# 51.net
KiCad netlist of a schematic drawn in EasyEDA Pro
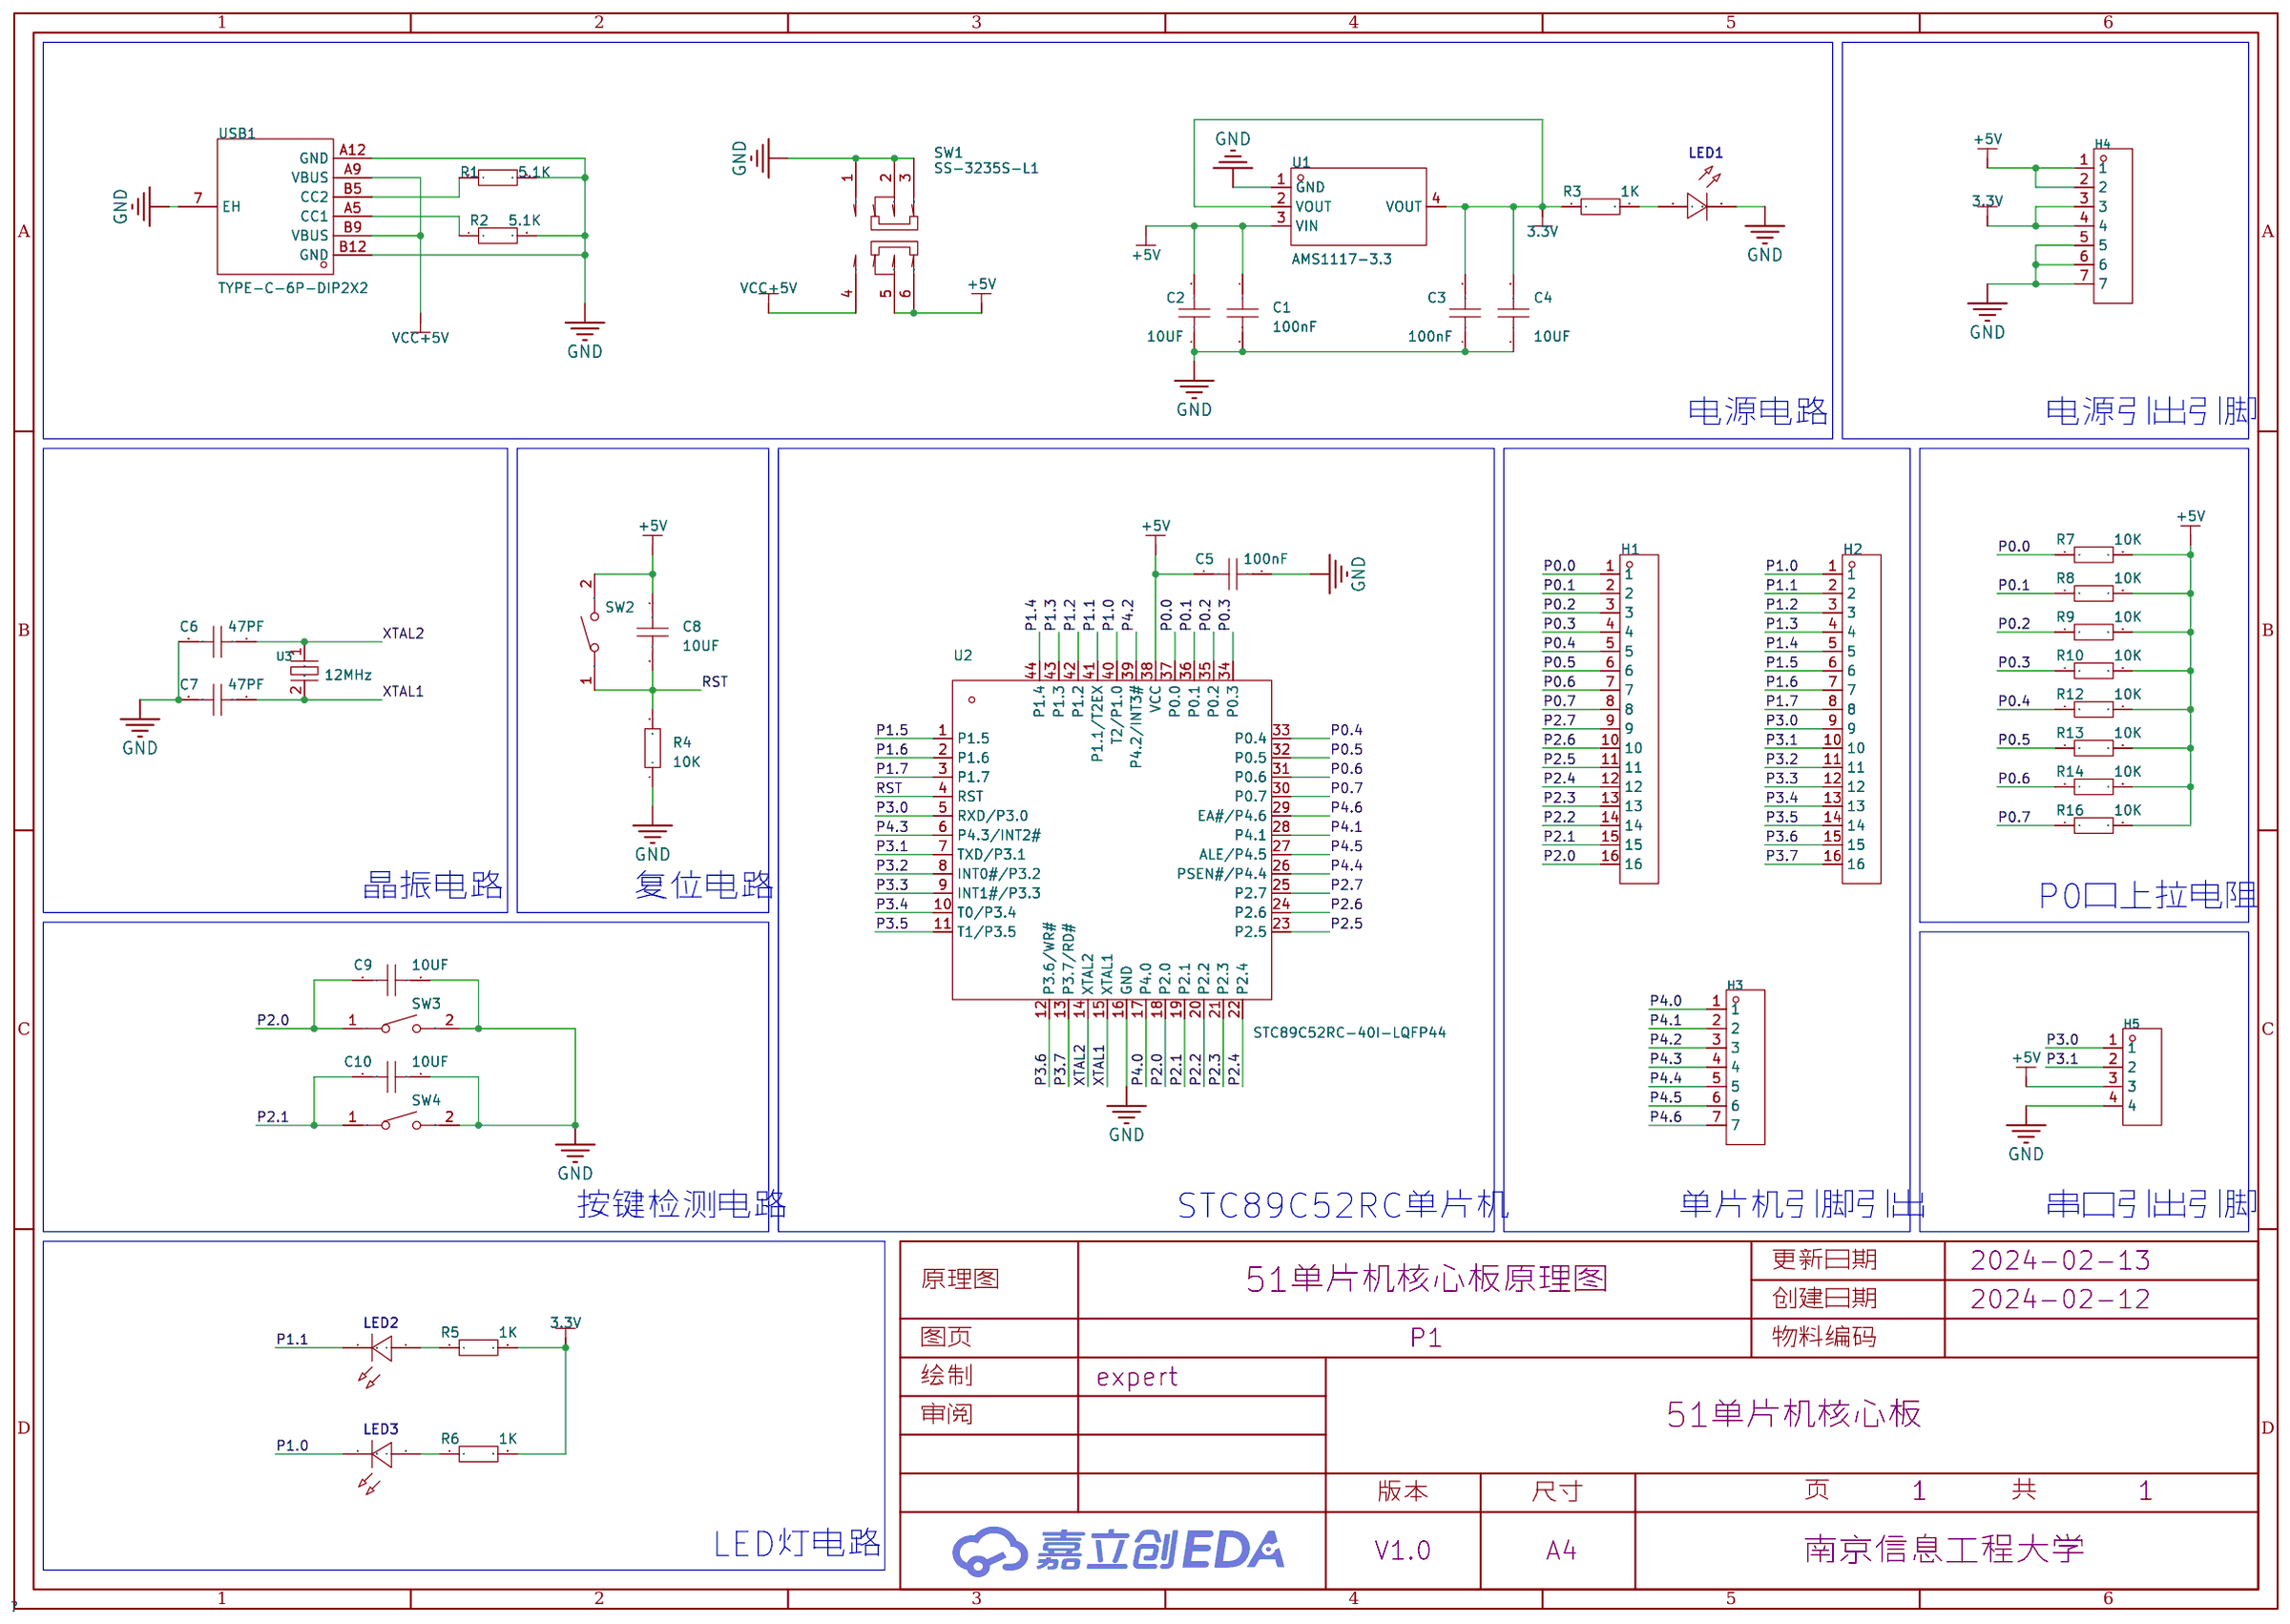
[diagram p0: schematic sheet]

(export (version "E")
  (design (tool "Eeschema 10.0.6"))
  (components
    (comp (ref "C1")
      (value "100nF")
      (footprint "easyedapro:C0805")
      (libsource (lib "easyedapro") (part "CapAcitance"))
    )
    (comp (ref "C2")
      (value "10UF")
      (footprint "easyedapro:C0805")
      (libsource (lib "easyedapro") (part "CapAcitance"))
    )
    (comp (ref "C3")
      (value "100nF")
      (footprint "easyedapro:C0805")
      (libsource (lib "easyedapro") (part "CapAcitance"))
    )
    (comp (ref "C4")
      (value "10UF")
      (footprint "easyedapro:C0805")
      (libsource (lib "easyedapro") (part "CapAcitance"))
    )
    (comp (ref "C5")
      (value "100nF")
      (footprint "easyedapro:C0805")
      (libsource (lib "easyedapro") (part "CapAcitance"))
    )
    (comp (ref "C6")
      (value "47PF")
      (footprint "easyedapro:C0805")
      (libsource (lib "easyedapro") (part "CapAcitance"))
    )
    (comp (ref "C7")
      (value "47PF")
      (footprint "easyedapro:C0805")
      (libsource (lib "easyedapro") (part "CapAcitance"))
    )
    (comp (ref "C8")
      (value "10UF")
      (footprint "easyedapro:C0805")
      (libsource (lib "easyedapro") (part "CapAcitance"))
    )
    (comp (ref "C9")
      (value "10UF")
      (footprint "easyedapro:C0805")
      (libsource (lib "easyedapro") (part "CapAcitance"))
    )
    (comp (ref "C10")
      (value "10UF")
      (footprint "easyedapro:C0805")
      (libsource (lib "easyedapro") (part "CapAcitance"))
    )
    (comp (ref "H1")
      (value "~")
      (footprint "easyedapro:HDR-TH_16P-P2.54-V-M")
      (libsource (lib "easyedapro") (part "HDR_2.54-1x16P"))
    )
    (comp (ref "H2")
      (value "~")
      (footprint "easyedapro:HDR-TH_16P-P2.54-V-M")
      (libsource (lib "easyedapro") (part "HDR_2.54-1x16P"))
    )
    (comp (ref "H3")
      (value "~")
      (footprint "easyedapro:HDR-TH_7P-P2.54-V-M")
      (libsource (lib "easyedapro") (part "PZ254V-11-07P"))
    )
    (comp (ref "H4")
      (value "~")
      (footprint "easyedapro:HDR-TH_7P-P2.54-V-M")
      (libsource (lib "easyedapro") (part "PZ254V-11-07P"))
    )
    (comp (ref "H5")
      (value "~")
      (footprint "easyedapro:HDR-TH_4P-P2.54-V-M")
      (libsource (lib "easyedapro") (part "PZ254V-11-04P"))
    )
    (comp (ref "LED1")
      (value "~")
      (footprint "easyedapro:LED_0805")
      (libsource (lib "easyedapro") (part "LED_G"))
    )
    (comp (ref "LED2")
      (value "~")
      (footprint "easyedapro:LED_0805")
      (libsource (lib "easyedapro") (part "LED_G"))
    )
    (comp (ref "LED3")
      (value "~")
      (footprint "easyedapro:LED_0805")
      (libsource (lib "easyedapro") (part "LED_G"))
    )
    (comp (ref "R1") (value "5.1K") (footprint "easyedapro:R0805") (libsource (lib "easyedapro") (part "电阻")))
    (comp (ref "R2") (value "5.1K") (footprint "easyedapro:R0805") (libsource (lib "easyedapro") (part "电阻")))
    (comp (ref "R3") (value "1K") (footprint "easyedapro:R0805") (libsource (lib "easyedapro") (part "电阻")))
    (comp (ref "R4") (value "10K") (footprint "easyedapro:R0805") (libsource (lib "easyedapro") (part "电阻")))
    (comp (ref "R5") (value "1K") (footprint "easyedapro:R0805") (libsource (lib "easyedapro") (part "电阻")))
    (comp (ref "R6") (value "1K") (footprint "easyedapro:R0805") (libsource (lib "easyedapro") (part "电阻")))
    (comp (ref "R7") (value "10K") (footprint "easyedapro:R0805") (libsource (lib "easyedapro") (part "电阻")))
    (comp (ref "R8") (value "10K") (footprint "easyedapro:R0805") (libsource (lib "easyedapro") (part "电阻")))
    (comp (ref "R9") (value "10K") (footprint "easyedapro:R0805") (libsource (lib "easyedapro") (part "电阻")))
    (comp (ref "R10") (value "10K") (footprint "easyedapro:R0805") (libsource (lib "easyedapro") (part "电阻")))
    (comp (ref "R12") (value "10K") (footprint "easyedapro:R0805") (libsource (lib "easyedapro") (part "电阻")))
    (comp (ref "R13") (value "10K") (footprint "easyedapro:R0805") (libsource (lib "easyedapro") (part "电阻")))
    (comp (ref "R14") (value "10K") (footprint "easyedapro:R0805") (libsource (lib "easyedapro") (part "电阻")))
    (comp (ref "R16") (value "10K") (footprint "easyedapro:R0805") (libsource (lib "easyedapro") (part "电阻")))
    (comp (ref "SW1")
      (value "SS-3235S-L1")
      (footprint "easyedapro:SW-SMD_SS-3235S-LX")
      (description "电路结构:双刀双掷;安装方式:卧贴;开关颜色:黑色;额定电流(DC):50mA;额定电压(DC):12V;额定电流(AC):50mA;额定电压(AC):12V;机械寿命:1万次;")
      (fields (field (name "Manufacturer") "XKB Connectivity(中国星坤)"))
      (libsource (lib "easyedapro") (part "SS-3235S-L1"))
    )
    (comp (ref "SW2")
      (value "轻触按键3*4*H")
      (footprint "easyedapro:SW-SMD_L4.0-W2.9-LS5.0")
      (libsource (lib "easyedapro") (part "轻触按键3*4*H"))
    )
    (comp (ref "SW3")
      (value "轻触按键3*4*H")
      (footprint "easyedapro:SW-SMD_L4.0-W2.9-LS5.0")
      (libsource (lib "easyedapro") (part "轻触按键3*4*H"))
    )
    (comp (ref "SW4")
      (value "轻触按键3*4*H")
      (footprint "easyedapro:SW-SMD_L4.0-W2.9-LS5.0")
      (libsource (lib "easyedapro") (part "轻触按键3*4*H"))
    )
    (comp (ref "U1")
      (value "AMS1117-3.3")
      (footprint "easyedapro:SOT-223-3_L6.5-W3.4-P2.30-LS7.0-BR")
      (description "输出类型:固定;最大输入电压:-;输出电压:3.3V;最大输出电流:1A;电源纹波抑制比(PSRR):72dB@(120Hz);输出极性:正极;")
      (fields (field (name "Manufacturer") "AMS"))
      (libsource (lib "easyedapro") (part "AMS1117-3.3"))
    )
    (comp (ref "U2")
      (value "STC89C52RC-40I-LQFP44")
      (footprint "easyedapro:LQFP-44_L10.0-W10.0-P0.80-LS12.0-BL")
      (description "CPU内核:51系列;程序存储容量:8KB;RAM总容量:512Byte;GPIO端口数量:39;工作电压范围:3.3V~5.5V;CPU最大主频:-;程序存储器类型:FLASH;")
      (fields (field (name "Manufacturer") "STC(宏晶)"))
      (libsource (lib "easyedapro") (part "STC89C52RC-40I_C8707"))
    )
    (comp (ref "U3")
      (value "12MHz")
      (footprint "easyedapro:CRYSTAL-SMD_L11.4-W4.7-LS12.7")
      (description "频率:12MHz;常温频差:±30ppm;外接负载电容:18pF;频率稳定度(全温):±35ppm;")
      (fields
        (field (name "Manufacturer Part") "ABLS-12.000MHZ-B4H-T")
        (field (name "Manufacturer") "ABRACON")
      )
      (libsource (lib "easyedapro") (part "ABLS-12.000MHZ-B4H-T"))
    )
    (comp (ref "USB1")
      (value "TYPE-C-6P-DIP2X2")
      (footprint "easyedapro:TYPE-C-SMD_TYPE-C-6P")
      (libsource (lib "easyedapro") (part "TYPE-C-6P-DIP2X2"))
    )
  )
  (nets
    (net (code "1") (name "+5V") (class "Default")
      (node (ref "C1") (pin "1") (pinfunction "1_1") (pintype "input"))
      (node (ref "C2") (pin "2") (pinfunction "2_2") (pintype "input"))
      (node (ref "C5") (pin "1") (pinfunction "1_1") (pintype "input"))
      (node (ref "C8") (pin "1") (pinfunction "1_1") (pintype "input"))
      (node (ref "H4") (pin "1") (pinfunction "1_1") (pintype "input"))
      (node (ref "H4") (pin "2") (pinfunction "2_2") (pintype "input"))
      (node (ref "H5") (pin "3") (pinfunction "3_3") (pintype "input"))
      (node (ref "R10") (pin "2") (pinfunction "2_2") (pintype "input"))
      (node (ref "R12") (pin "2") (pinfunction "2_2") (pintype "input"))
      (node (ref "R13") (pin "2") (pinfunction "2_2") (pintype "input"))
      (node (ref "R14") (pin "2") (pinfunction "2_2") (pintype "input"))
      (node (ref "R16") (pin "2") (pinfunction "2_2") (pintype "input"))
      (node (ref "R7") (pin "2") (pinfunction "2_2") (pintype "input"))
      (node (ref "R8") (pin "2") (pinfunction "2_2") (pintype "input"))
      (node (ref "R9") (pin "2") (pinfunction "2_2") (pintype "input"))
      (node (ref "SW1") (pin "5") (pinfunction "5_5") (pintype "unspecified"))
      (node (ref "SW1") (pin "6") (pinfunction "6_6") (pintype "unspecified"))
      (node (ref "SW2") (pin "2") (pinfunction "2_2") (pintype "input"))
      (node (ref "U1") (pin "3") (pinfunction "VIN_3") (pintype "unspecified"))
      (node (ref "U2") (pin "38") (pinfunction "VCC_38") (pintype "unspecified"))
    )
    (net (code "2") (name "/P0.0") (class "Default")
      (node (ref "H1") (pin "1") (pinfunction "1_1") (pintype "input"))
      (node (ref "R7") (pin "1") (pinfunction "1_1") (pintype "input"))
      (node (ref "U2") (pin "37") (pinfunction "P0.0_37") (pintype "unspecified"))
    )
    (net (code "3") (name "/P0.1") (class "Default")
      (node (ref "H1") (pin "2") (pinfunction "2_2") (pintype "input"))
      (node (ref "R8") (pin "1") (pinfunction "1_1") (pintype "input"))
      (node (ref "U2") (pin "36") (pinfunction "P0.1_36") (pintype "unspecified"))
    )
    (net (code "4") (name "/P0.2") (class "Default")
      (node (ref "H1") (pin "3") (pinfunction "3_3") (pintype "input"))
      (node (ref "R9") (pin "1") (pinfunction "1_1") (pintype "input"))
      (node (ref "U2") (pin "35") (pinfunction "P0.2_35") (pintype "unspecified"))
    )
    (net (code "5") (name "/P0.3") (class "Default")
      (node (ref "H1") (pin "4") (pinfunction "4_4") (pintype "input"))
      (node (ref "R10") (pin "1") (pinfunction "1_1") (pintype "input"))
      (node (ref "U2") (pin "34") (pinfunction "P0.3_34") (pintype "unspecified"))
    )
    (net (code "6") (name "/P0.4") (class "Default")
      (node (ref "H1") (pin "5") (pinfunction "5_5") (pintype "input"))
      (node (ref "R12") (pin "1") (pinfunction "1_1") (pintype "input"))
      (node (ref "U2") (pin "33") (pinfunction "P0.4_33") (pintype "unspecified"))
    )
    (net (code "7") (name "/P0.5") (class "Default")
      (node (ref "H1") (pin "6") (pinfunction "6_6") (pintype "input"))
      (node (ref "R13") (pin "1") (pinfunction "1_1") (pintype "input"))
      (node (ref "U2") (pin "32") (pinfunction "P0.5_32") (pintype "unspecified"))
    )
    (net (code "8") (name "/P0.6") (class "Default")
      (node (ref "H1") (pin "7") (pinfunction "7_7") (pintype "input"))
      (node (ref "R14") (pin "1") (pinfunction "1_1") (pintype "input"))
      (node (ref "U2") (pin "31") (pinfunction "P0.6_31") (pintype "unspecified"))
    )
    (net (code "9") (name "/P0.7") (class "Default")
      (node (ref "H1") (pin "8") (pinfunction "8_8") (pintype "input"))
      (node (ref "R16") (pin "1") (pinfunction "1_1") (pintype "input"))
      (node (ref "U2") (pin "30") (pinfunction "P0.7_30") (pintype "unspecified"))
    )
    (net (code "10") (name "/P1.0") (class "Default")
      (node (ref "H2") (pin "1") (pinfunction "1_1") (pintype "input"))
      (node (ref "LED3") (pin "1") (pinfunction "C_1") (pintype "input"))
      (node (ref "U2") (pin "40") (pinfunction "T2/P1.0_40") (pintype "unspecified"))
    )
    (net (code "11") (name "/P1.1") (class "Default")
      (node (ref "H2") (pin "2") (pinfunction "2_2") (pintype "input"))
      (node (ref "LED2") (pin "1") (pinfunction "C_1") (pintype "input"))
      (node (ref "U2") (pin "41") (pinfunction "P1.1/T2EX_41") (pintype "unspecified"))
    )
    (net (code "12") (name "/P1.2") (class "Default")
      (node (ref "H2") (pin "3") (pinfunction "3_3") (pintype "input"))
      (node (ref "U2") (pin "42") (pinfunction "P1.2_42") (pintype "unspecified"))
    )
    (net (code "13") (name "/P1.3") (class "Default")
      (node (ref "H2") (pin "4") (pinfunction "4_4") (pintype "input"))
      (node (ref "U2") (pin "43") (pinfunction "P1.3_43") (pintype "unspecified"))
    )
    (net (code "14") (name "/P1.4") (class "Default")
      (node (ref "H2") (pin "5") (pinfunction "5_5") (pintype "input"))
      (node (ref "U2") (pin "44") (pinfunction "P1.4_44") (pintype "unspecified"))
    )
    (net (code "15") (name "/P1.5") (class "Default")
      (node (ref "H2") (pin "6") (pinfunction "6_6") (pintype "input"))
      (node (ref "U2") (pin "1") (pinfunction "P1.5_1") (pintype "unspecified"))
    )
    (net (code "16") (name "/P1.6") (class "Default")
      (node (ref "H2") (pin "7") (pinfunction "7_7") (pintype "input"))
      (node (ref "U2") (pin "2") (pinfunction "P1.6_2") (pintype "unspecified"))
    )
    (net (code "17") (name "/P1.7") (class "Default")
      (node (ref "H2") (pin "8") (pinfunction "8_8") (pintype "input"))
      (node (ref "U2") (pin "3") (pinfunction "P1.7_3") (pintype "unspecified"))
    )
    (net (code "18") (name "/P2.0") (class "Default")
      (node (ref "C9") (pin "1") (pinfunction "1_1") (pintype "input"))
      (node (ref "H1") (pin "16") (pinfunction "16_16") (pintype "input"))
      (node (ref "SW3") (pin "1") (pinfunction "1_1") (pintype "input"))
      (node (ref "U2") (pin "18") (pinfunction "P2.0_18") (pintype "unspecified"))
    )
    (net (code "19") (name "/P2.1") (class "Default")
      (node (ref "C10") (pin "1") (pinfunction "1_1") (pintype "input"))
      (node (ref "H1") (pin "15") (pinfunction "15_15") (pintype "input"))
      (node (ref "SW4") (pin "1") (pinfunction "1_1") (pintype "input"))
      (node (ref "U2") (pin "19") (pinfunction "P2.1_19") (pintype "unspecified"))
    )
    (net (code "20") (name "/P2.2") (class "Default")
      (node (ref "H1") (pin "14") (pinfunction "14_14") (pintype "input"))
      (node (ref "U2") (pin "20") (pinfunction "P2.2_20") (pintype "unspecified"))
    )
    (net (code "21") (name "/P2.3") (class "Default")
      (node (ref "H1") (pin "13") (pinfunction "13_13") (pintype "input"))
      (node (ref "U2") (pin "21") (pinfunction "P2.3_21") (pintype "unspecified"))
    )
    (net (code "22") (name "/P2.4") (class "Default")
      (node (ref "H1") (pin "12") (pinfunction "12_12") (pintype "input"))
      (node (ref "U2") (pin "22") (pinfunction "P2.4_22") (pintype "unspecified"))
    )
    (net (code "23") (name "/P2.5") (class "Default")
      (node (ref "H1") (pin "11") (pinfunction "11_11") (pintype "input"))
      (node (ref "U2") (pin "23") (pinfunction "P2.5_23") (pintype "unspecified"))
    )
    (net (code "24") (name "/P2.6") (class "Default")
      (node (ref "H1") (pin "10") (pinfunction "10_10") (pintype "input"))
      (node (ref "U2") (pin "24") (pinfunction "P2.6_24") (pintype "unspecified"))
    )
    (net (code "25") (name "/P2.7") (class "Default")
      (node (ref "H1") (pin "9") (pinfunction "9_9") (pintype "input"))
      (node (ref "U2") (pin "25") (pinfunction "P2.7_25") (pintype "unspecified"))
    )
    (net (code "26") (name "/P3.0") (class "Default")
      (node (ref "H2") (pin "9") (pinfunction "9_9") (pintype "input"))
      (node (ref "H5") (pin "1") (pinfunction "1_1") (pintype "input"))
      (node (ref "U2") (pin "5") (pinfunction "RXD/P3.0_5") (pintype "unspecified"))
    )
    (net (code "27") (name "/P3.1") (class "Default")
      (node (ref "H2") (pin "10") (pinfunction "10_10") (pintype "input"))
      (node (ref "H5") (pin "2") (pinfunction "2_2") (pintype "input"))
      (node (ref "U2") (pin "7") (pinfunction "TXD/P3.1_7") (pintype "unspecified"))
    )
    (net (code "28") (name "/P3.2") (class "Default")
      (node (ref "H2") (pin "11") (pinfunction "11_11") (pintype "input"))
      (node (ref "U2") (pin "8") (pinfunction "INT0#/P3.2_8") (pintype "unspecified"))
    )
    (net (code "29") (name "/P3.3") (class "Default")
      (node (ref "H2") (pin "12") (pinfunction "12_12") (pintype "input"))
      (node (ref "U2") (pin "9") (pinfunction "INT1#/P3.3_9") (pintype "unspecified"))
    )
    (net (code "30") (name "/P3.4") (class "Default")
      (node (ref "H2") (pin "13") (pinfunction "13_13") (pintype "input"))
      (node (ref "U2") (pin "10") (pinfunction "T0/P3.4_10") (pintype "unspecified"))
    )
    (net (code "31") (name "/P3.5") (class "Default")
      (node (ref "H2") (pin "14") (pinfunction "14_14") (pintype "input"))
      (node (ref "U2") (pin "11") (pinfunction "T1/P3.5_11") (pintype "unspecified"))
    )
    (net (code "32") (name "/P3.6") (class "Default")
      (node (ref "H2") (pin "15") (pinfunction "15_15") (pintype "input"))
      (node (ref "U2") (pin "12") (pinfunction "P3.6/WR#_12") (pintype "unspecified"))
    )
    (net (code "33") (name "/P3.7") (class "Default")
      (node (ref "H2") (pin "16") (pinfunction "16_16") (pintype "input"))
      (node (ref "U2") (pin "13") (pinfunction "P3.7/RD#_13") (pintype "unspecified"))
    )
    (net (code "34") (name "/P4.0") (class "Default")
      (node (ref "H3") (pin "1") (pinfunction "1_1") (pintype "input"))
      (node (ref "U2") (pin "17") (pinfunction "P4.0_17") (pintype "unspecified"))
    )
    (net (code "35") (name "/P4.1") (class "Default")
      (node (ref "H3") (pin "2") (pinfunction "2_2") (pintype "input"))
      (node (ref "U2") (pin "28") (pinfunction "P4.1_28") (pintype "unspecified"))
    )
    (net (code "36") (name "/P4.2") (class "Default")
      (node (ref "H3") (pin "3") (pinfunction "3_3") (pintype "input"))
      (node (ref "U2") (pin "39") (pinfunction "P4.2/INT3#_39") (pintype "unspecified"))
    )
    (net (code "37") (name "/P4.3") (class "Default")
      (node (ref "H3") (pin "4") (pinfunction "4_4") (pintype "input"))
      (node (ref "U2") (pin "6") (pinfunction "P4.3/INT2#_6") (pintype "unspecified"))
    )
    (net (code "38") (name "/P4.4") (class "Default")
      (node (ref "H3") (pin "5") (pinfunction "5_5") (pintype "input"))
      (node (ref "U2") (pin "26") (pinfunction "PSEN#/P4.4_26") (pintype "unspecified"))
    )
    (net (code "39") (name "/P4.5") (class "Default")
      (node (ref "H3") (pin "6") (pinfunction "6_6") (pintype "input"))
      (node (ref "U2") (pin "27") (pinfunction "ALE/P4.5_27") (pintype "unspecified"))
    )
    (net (code "40") (name "/P4.6") (class "Default")
      (node (ref "H3") (pin "7") (pinfunction "7_7") (pintype "input"))
      (node (ref "U2") (pin "29") (pinfunction "EA#/P4.6_29") (pintype "unspecified"))
    )
    (net (code "41") (name "/RST") (class "Default")
      (node (ref "C8") (pin "2") (pinfunction "2_2") (pintype "input"))
      (node (ref "R4") (pin "2") (pinfunction "2_2") (pintype "input"))
      (node (ref "SW2") (pin "1") (pinfunction "1_1") (pintype "input"))
      (node (ref "U2") (pin "4") (pinfunction "RST_4") (pintype "unspecified"))
    )
    (net (code "42") (name "/XTAL1") (class "Default")
      (node (ref "C7") (pin "1") (pinfunction "1_1") (pintype "input"))
      (node (ref "U2") (pin "15") (pinfunction "XTAL1_15") (pintype "unspecified"))
      (node (ref "U3") (pin "2") (pinfunction "GND_2") (pintype "input"))
    )
    (net (code "43") (name "/XTAL2") (class "Default")
      (node (ref "C6") (pin "1") (pinfunction "1_1") (pintype "input"))
      (node (ref "U2") (pin "14") (pinfunction "XTAL2_14") (pintype "unspecified"))
      (node (ref "U3") (pin "1") (pinfunction "1_1") (pintype "input"))
    )
    (net (code "44") (name "3.3V") (class "Default")
      (node (ref "C3") (pin "2") (pinfunction "2_2") (pintype "input"))
      (node (ref "C4") (pin "2") (pinfunction "2_2") (pintype "input"))
      (node (ref "H4") (pin "3") (pinfunction "3_3") (pintype "input"))
      (node (ref "H4") (pin "4") (pinfunction "4_4") (pintype "input"))
      (node (ref "R3") (pin "1") (pinfunction "1_1") (pintype "input"))
      (node (ref "R5") (pin "2") (pinfunction "2_2") (pintype "input"))
      (node (ref "R6") (pin "2") (pinfunction "2_2") (pintype "input"))
      (node (ref "U1") (pin "2") (pinfunction "VOUT_2") (pintype "unspecified"))
      (node (ref "U1") (pin "4") (pinfunction "VOUT_4") (pintype "unspecified"))
    )
    (net (code "45") (name "GND") (class "Default")
      (node (ref "C1") (pin "2") (pinfunction "2_2") (pintype "input"))
      (node (ref "C10") (pin "2") (pinfunction "2_2") (pintype "input"))
      (node (ref "C2") (pin "1") (pinfunction "1_1") (pintype "input"))
      (node (ref "C3") (pin "1") (pinfunction "1_1") (pintype "input"))
      (node (ref "C4") (pin "1") (pinfunction "1_1") (pintype "input"))
      (node (ref "C5") (pin "2") (pinfunction "2_2") (pintype "input"))
      (node (ref "C6") (pin "2") (pinfunction "2_2") (pintype "input"))
      (node (ref "C7") (pin "2") (pinfunction "2_2") (pintype "input"))
      (node (ref "C9") (pin "2") (pinfunction "2_2") (pintype "input"))
      (node (ref "H4") (pin "5") (pinfunction "5_5") (pintype "input"))
      (node (ref "H4") (pin "6") (pinfunction "6_6") (pintype "input"))
      (node (ref "H4") (pin "7") (pinfunction "7_7") (pintype "input"))
      (node (ref "H5") (pin "4") (pinfunction "4_4") (pintype "input"))
      (node (ref "LED1") (pin "1") (pinfunction "C_1") (pintype "input"))
      (node (ref "R1") (pin "2") (pinfunction "2_2") (pintype "input"))
      (node (ref "R2") (pin "2") (pinfunction "2_2") (pintype "input"))
      (node (ref "R4") (pin "1") (pinfunction "1_1") (pintype "input"))
      (node (ref "SW1") (pin "1") (pinfunction "1_1") (pintype "unspecified"))
      (node (ref "SW1") (pin "2") (pinfunction "2_2") (pintype "unspecified"))
      (node (ref "SW1") (pin "3") (pinfunction "3_3") (pintype "unspecified"))
      (node (ref "SW3") (pin "2") (pinfunction "2_2") (pintype "input"))
      (node (ref "SW4") (pin "2") (pinfunction "2_2") (pintype "input"))
      (node (ref "U1") (pin "1") (pinfunction "GND_1") (pintype "unspecified"))
      (node (ref "U2") (pin "16") (pinfunction "GND_16") (pintype "unspecified"))
      (node (ref "USB1") (pin "7") (pinfunction "EH_7") (pintype "input"))
      (node (ref "USB1") (pin "A12") (pinfunction "GND_A12") (pintype "input"))
      (node (ref "USB1") (pin "B12") (pinfunction "GND_B12") (pintype "input"))
    )
    (net (code "46") (name "Net-(LED1-A)") (class "Default")
      (node (ref "LED1") (pin "2") (pinfunction "A_2") (pintype "input"))
      (node (ref "R3") (pin "2") (pinfunction "2_2") (pintype "input"))
    )
    (net (code "47") (name "Net-(LED2-A)") (class "Default")
      (node (ref "LED2") (pin "2") (pinfunction "A_2") (pintype "input"))
      (node (ref "R5") (pin "1") (pinfunction "1_1") (pintype "input"))
    )
    (net (code "48") (name "Net-(LED3-A)") (class "Default")
      (node (ref "LED3") (pin "2") (pinfunction "A_2") (pintype "input"))
      (node (ref "R6") (pin "1") (pinfunction "1_1") (pintype "input"))
    )
    (net (code "49") (name "Net-(USB1-CC1)") (class "Default")
      (node (ref "R2") (pin "1") (pinfunction "1_1") (pintype "input"))
      (node (ref "USB1") (pin "A5") (pinfunction "CC1_A5") (pintype "input"))
    )
    (net (code "50") (name "Net-(USB1-CC2)") (class "Default")
      (node (ref "R1") (pin "1") (pinfunction "1_1") (pintype "input"))
      (node (ref "USB1") (pin "B5") (pinfunction "CC2_B5") (pintype "input"))
    )
    (net (code "51") (name "VCC+5V") (class "Default")
      (node (ref "SW1") (pin "4") (pinfunction "4_4") (pintype "unspecified"))
      (node (ref "USB1") (pin "A9") (pinfunction "VBUS_A9") (pintype "input"))
      (node (ref "USB1") (pin "B9") (pinfunction "VBUS_B9") (pintype "input"))
    )
  )
)
